# APA106_uno_shield.net
KiCad netlist of a schematic drawn in EAGLE
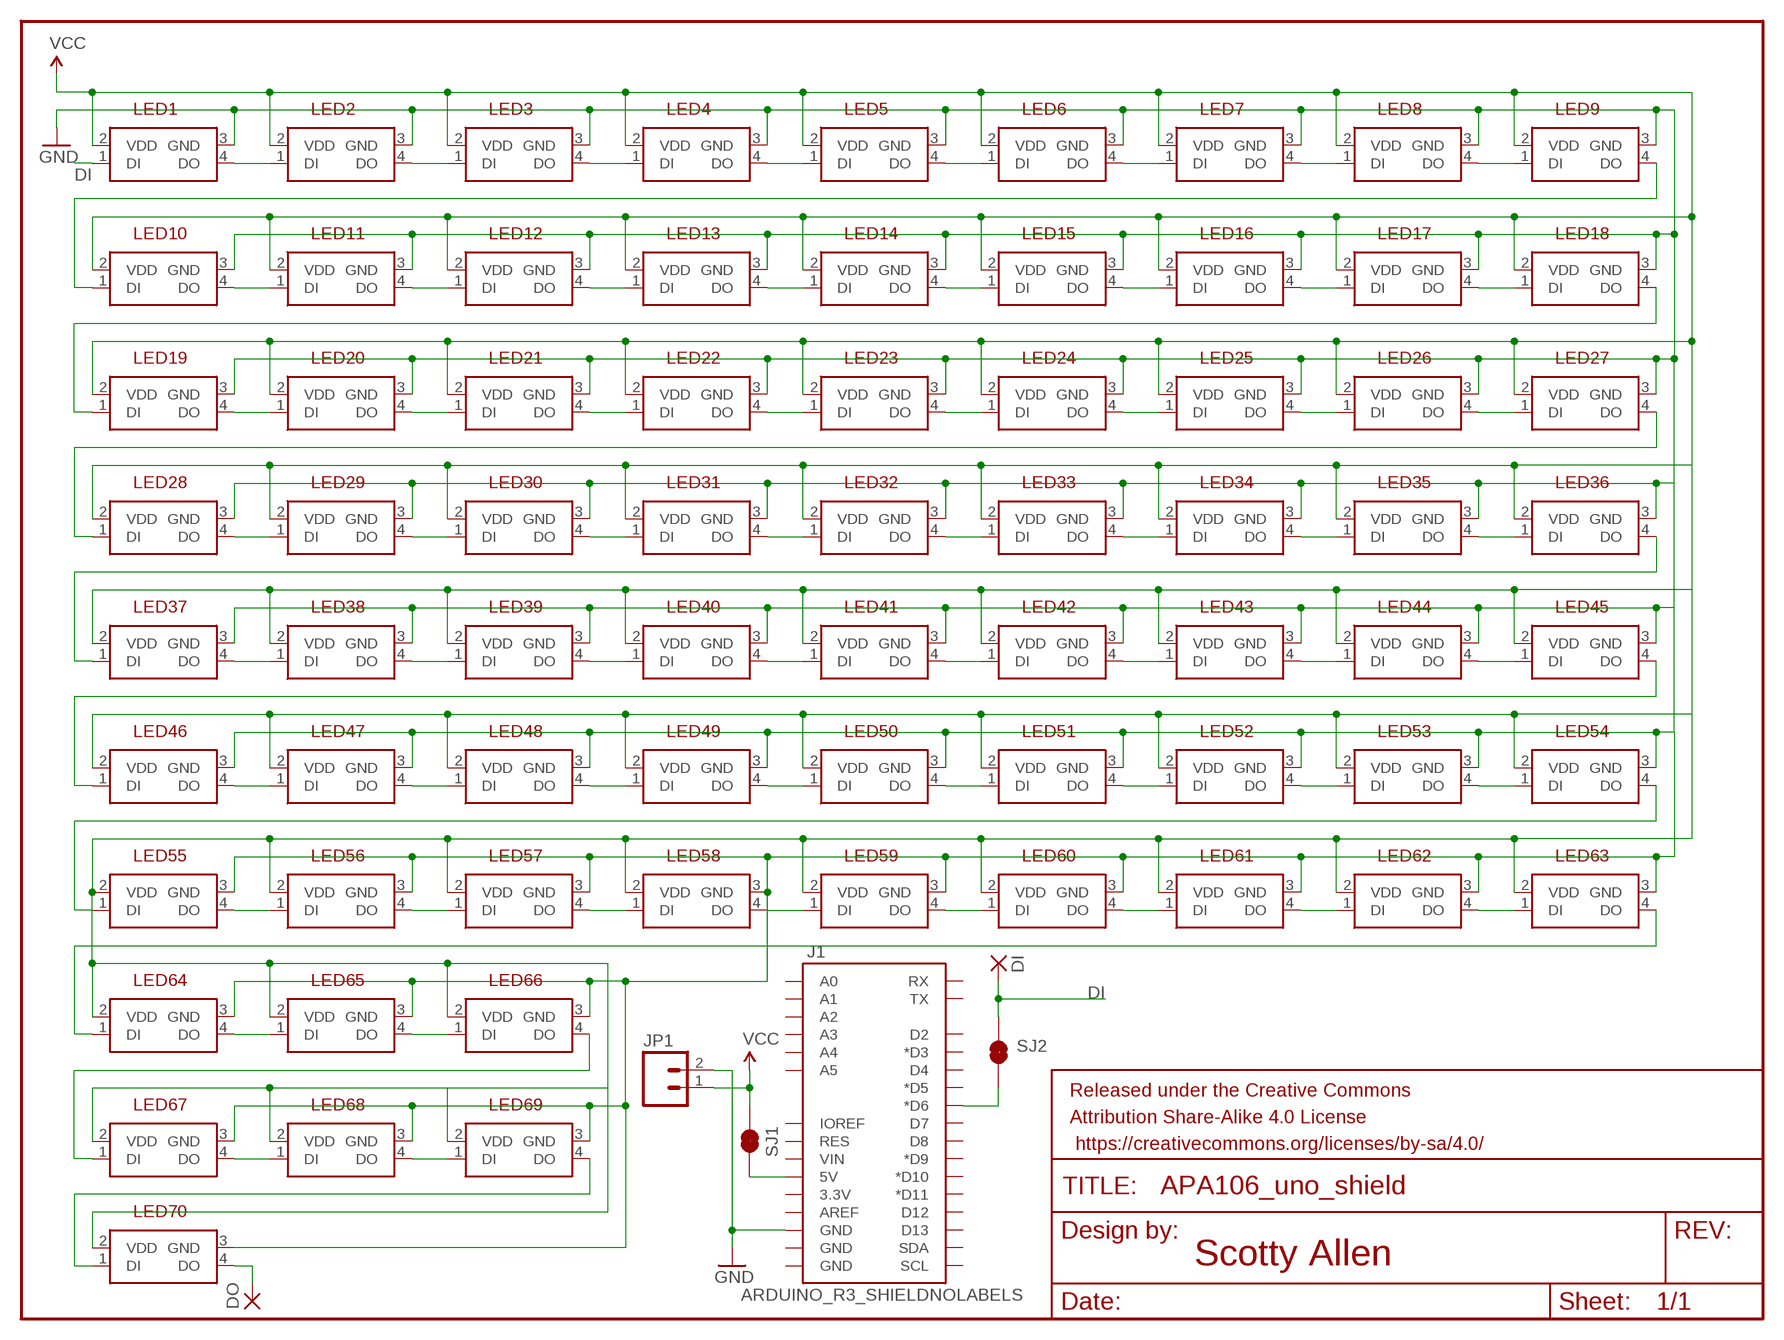
[diagram p0: schematic, sheet 1]

(export (version "E")
  (design (tool "Eeschema 10.0.6"))
  (components
    (comp (ref "DI")
      (value "1,6/0,9")
      (footprint "eagle-import:1,6_0,9")
      (libsource (lib "eagle-import") (part "1,6/0,9"))
    )
    (comp (ref "DO")
      (value "1,6/0,9")
      (footprint "eagle-import:1,6_0,9")
      (libsource (lib "eagle-import") (part "1,6/0,9"))
    )
    (comp (ref "FRAME1")
      (value "FRAME-LETTER")
      (footprint "eagle-import:CREATIVE_COMMONS")
      (libsource (lib "eagle-import") (part "FRAME-LETTER"))
    )
    (comp (ref "J1")
      (value "ARDUINO_R3_SHIELDNOLABELS")
      (footprint "eagle-import:UNO_R3_SHIELD_NOLABELS")
      (libsource (lib "eagle-import") (part "ARDUINO_R3_SHIELDNOLABELS"))
    )
    (comp (ref "JP1")
      (value "M02PTH")
      (footprint "eagle-import:1X02")
      (libsource (lib "eagle-import") (part "M02PTH"))
    )
    (comp (ref "LED1")
      (value "LED-APA106HOLE-OFFSET")
      (footprint "eagle-import:LED-5MM-4PIN-HOLE-OFFSET")
      (libsource (lib "eagle-import") (part "LED-APA106HOLE-OFFSET"))
    )
    (comp (ref "LED2")
      (value "LED-APA106HOLE-OFFSET")
      (footprint "eagle-import:LED-5MM-4PIN-HOLE-OFFSET")
      (libsource (lib "eagle-import") (part "LED-APA106HOLE-OFFSET"))
    )
    (comp (ref "LED3")
      (value "LED-APA106HOLE-OFFSET")
      (footprint "eagle-import:LED-5MM-4PIN-HOLE-OFFSET")
      (libsource (lib "eagle-import") (part "LED-APA106HOLE-OFFSET"))
    )
    (comp (ref "LED4")
      (value "LED-APA106HOLE-OFFSET")
      (footprint "eagle-import:LED-5MM-4PIN-HOLE-OFFSET")
      (libsource (lib "eagle-import") (part "LED-APA106HOLE-OFFSET"))
    )
    (comp (ref "LED5")
      (value "LED-APA106HOLE-OFFSET")
      (footprint "eagle-import:LED-5MM-4PIN-HOLE-OFFSET")
      (libsource (lib "eagle-import") (part "LED-APA106HOLE-OFFSET"))
    )
    (comp (ref "LED6")
      (value "LED-APA106HOLE-OFFSET")
      (footprint "eagle-import:LED-5MM-4PIN-HOLE-OFFSET")
      (libsource (lib "eagle-import") (part "LED-APA106HOLE-OFFSET"))
    )
    (comp (ref "LED7")
      (value "LED-APA106HOLE-OFFSET")
      (footprint "eagle-import:LED-5MM-4PIN-HOLE-OFFSET")
      (libsource (lib "eagle-import") (part "LED-APA106HOLE-OFFSET"))
    )
    (comp (ref "LED8")
      (value "LED-APA106HOLE-OFFSET")
      (footprint "eagle-import:LED-5MM-4PIN-HOLE-OFFSET")
      (libsource (lib "eagle-import") (part "LED-APA106HOLE-OFFSET"))
    )
    (comp (ref "LED9")
      (value "LED-APA106HOLE-OFFSET")
      (footprint "eagle-import:LED-5MM-4PIN-HOLE-OFFSET")
      (libsource (lib "eagle-import") (part "LED-APA106HOLE-OFFSET"))
    )
    (comp (ref "LED10")
      (value "LED-APA106HOLE-OFFSET")
      (footprint "eagle-import:LED-5MM-4PIN-HOLE-OFFSET")
      (libsource (lib "eagle-import") (part "LED-APA106HOLE-OFFSET"))
    )
    (comp (ref "LED11")
      (value "LED-APA106HOLE-OFFSET")
      (footprint "eagle-import:LED-5MM-4PIN-HOLE-OFFSET")
      (libsource (lib "eagle-import") (part "LED-APA106HOLE-OFFSET"))
    )
    (comp (ref "LED12")
      (value "LED-APA106HOLE-OFFSET")
      (footprint "eagle-import:LED-5MM-4PIN-HOLE-OFFSET")
      (libsource (lib "eagle-import") (part "LED-APA106HOLE-OFFSET"))
    )
    (comp (ref "LED13")
      (value "LED-APA106HOLE-OFFSET")
      (footprint "eagle-import:LED-5MM-4PIN-HOLE-OFFSET")
      (libsource (lib "eagle-import") (part "LED-APA106HOLE-OFFSET"))
    )
    (comp (ref "LED14")
      (value "LED-APA106HOLE-OFFSET")
      (footprint "eagle-import:LED-5MM-4PIN-HOLE-OFFSET")
      (libsource (lib "eagle-import") (part "LED-APA106HOLE-OFFSET"))
    )
    (comp (ref "LED15")
      (value "LED-APA106HOLE-OFFSET")
      (footprint "eagle-import:LED-5MM-4PIN-HOLE-OFFSET")
      (libsource (lib "eagle-import") (part "LED-APA106HOLE-OFFSET"))
    )
    (comp (ref "LED16")
      (value "LED-APA106HOLE-OFFSET")
      (footprint "eagle-import:LED-5MM-4PIN-HOLE-OFFSET")
      (libsource (lib "eagle-import") (part "LED-APA106HOLE-OFFSET"))
    )
    (comp (ref "LED17")
      (value "LED-APA106HOLE-OFFSET")
      (footprint "eagle-import:LED-5MM-4PIN-HOLE-OFFSET")
      (libsource (lib "eagle-import") (part "LED-APA106HOLE-OFFSET"))
    )
    (comp (ref "LED18")
      (value "LED-APA106HOLE-OFFSET")
      (footprint "eagle-import:LED-5MM-4PIN-HOLE-OFFSET")
      (libsource (lib "eagle-import") (part "LED-APA106HOLE-OFFSET"))
    )
    (comp (ref "LED19")
      (value "LED-APA106HOLE-OFFSET")
      (footprint "eagle-import:LED-5MM-4PIN-HOLE-OFFSET")
      (libsource (lib "eagle-import") (part "LED-APA106HOLE-OFFSET"))
    )
    (comp (ref "LED20")
      (value "LED-APA106HOLE-OFFSET")
      (footprint "eagle-import:LED-5MM-4PIN-HOLE-OFFSET")
      (libsource (lib "eagle-import") (part "LED-APA106HOLE-OFFSET"))
    )
    (comp (ref "LED21")
      (value "LED-APA106HOLE-OFFSET")
      (footprint "eagle-import:LED-5MM-4PIN-HOLE-OFFSET")
      (libsource (lib "eagle-import") (part "LED-APA106HOLE-OFFSET"))
    )
    (comp (ref "LED22")
      (value "LED-APA106HOLE-OFFSET")
      (footprint "eagle-import:LED-5MM-4PIN-HOLE-OFFSET")
      (libsource (lib "eagle-import") (part "LED-APA106HOLE-OFFSET"))
    )
    (comp (ref "LED23")
      (value "LED-APA106HOLE-OFFSET")
      (footprint "eagle-import:LED-5MM-4PIN-HOLE-OFFSET")
      (libsource (lib "eagle-import") (part "LED-APA106HOLE-OFFSET"))
    )
    (comp (ref "LED24")
      (value "LED-APA106HOLE-OFFSET")
      (footprint "eagle-import:LED-5MM-4PIN-HOLE-OFFSET")
      (libsource (lib "eagle-import") (part "LED-APA106HOLE-OFFSET"))
    )
    (comp (ref "LED25")
      (value "LED-APA106HOLE-OFFSET")
      (footprint "eagle-import:LED-5MM-4PIN-HOLE-OFFSET")
      (libsource (lib "eagle-import") (part "LED-APA106HOLE-OFFSET"))
    )
    (comp (ref "LED26")
      (value "LED-APA106HOLE-OFFSET")
      (footprint "eagle-import:LED-5MM-4PIN-HOLE-OFFSET")
      (libsource (lib "eagle-import") (part "LED-APA106HOLE-OFFSET"))
    )
    (comp (ref "LED27")
      (value "LED-APA106HOLE-OFFSET")
      (footprint "eagle-import:LED-5MM-4PIN-HOLE-OFFSET")
      (libsource (lib "eagle-import") (part "LED-APA106HOLE-OFFSET"))
    )
    (comp (ref "LED28")
      (value "LED-APA106HOLE-OFFSET")
      (footprint "eagle-import:LED-5MM-4PIN-HOLE-OFFSET")
      (libsource (lib "eagle-import") (part "LED-APA106HOLE-OFFSET"))
    )
    (comp (ref "LED29")
      (value "LED-APA106HOLE-OFFSET")
      (footprint "eagle-import:LED-5MM-4PIN-HOLE-OFFSET")
      (libsource (lib "eagle-import") (part "LED-APA106HOLE-OFFSET"))
    )
    (comp (ref "LED30")
      (value "LED-APA106HOLE-OFFSET")
      (footprint "eagle-import:LED-5MM-4PIN-HOLE-OFFSET")
      (libsource (lib "eagle-import") (part "LED-APA106HOLE-OFFSET"))
    )
    (comp (ref "LED31")
      (value "LED-APA106HOLE-OFFSET")
      (footprint "eagle-import:LED-5MM-4PIN-HOLE-OFFSET")
      (libsource (lib "eagle-import") (part "LED-APA106HOLE-OFFSET"))
    )
    (comp (ref "LED32")
      (value "LED-APA106HOLE-OFFSET")
      (footprint "eagle-import:LED-5MM-4PIN-HOLE-OFFSET")
      (libsource (lib "eagle-import") (part "LED-APA106HOLE-OFFSET"))
    )
    (comp (ref "LED33")
      (value "LED-APA106HOLE-OFFSET")
      (footprint "eagle-import:LED-5MM-4PIN-HOLE-OFFSET")
      (libsource (lib "eagle-import") (part "LED-APA106HOLE-OFFSET"))
    )
    (comp (ref "LED34")
      (value "LED-APA106HOLE-OFFSET")
      (footprint "eagle-import:LED-5MM-4PIN-HOLE-OFFSET")
      (libsource (lib "eagle-import") (part "LED-APA106HOLE-OFFSET"))
    )
    (comp (ref "LED35")
      (value "LED-APA106HOLE-OFFSET")
      (footprint "eagle-import:LED-5MM-4PIN-HOLE-OFFSET")
      (libsource (lib "eagle-import") (part "LED-APA106HOLE-OFFSET"))
    )
    (comp (ref "LED36")
      (value "LED-APA106HOLE-OFFSET")
      (footprint "eagle-import:LED-5MM-4PIN-HOLE-OFFSET")
      (libsource (lib "eagle-import") (part "LED-APA106HOLE-OFFSET"))
    )
    (comp (ref "LED37")
      (value "LED-APA106HOLE-OFFSET")
      (footprint "eagle-import:LED-5MM-4PIN-HOLE-OFFSET")
      (libsource (lib "eagle-import") (part "LED-APA106HOLE-OFFSET"))
    )
    (comp (ref "LED38")
      (value "LED-APA106HOLE-OFFSET")
      (footprint "eagle-import:LED-5MM-4PIN-HOLE-OFFSET")
      (libsource (lib "eagle-import") (part "LED-APA106HOLE-OFFSET"))
    )
    (comp (ref "LED39")
      (value "LED-APA106HOLE-OFFSET")
      (footprint "eagle-import:LED-5MM-4PIN-HOLE-OFFSET")
      (libsource (lib "eagle-import") (part "LED-APA106HOLE-OFFSET"))
    )
    (comp (ref "LED40")
      (value "LED-APA106HOLE-OFFSET")
      (footprint "eagle-import:LED-5MM-4PIN-HOLE-OFFSET")
      (libsource (lib "eagle-import") (part "LED-APA106HOLE-OFFSET"))
    )
    (comp (ref "LED41")
      (value "LED-APA106HOLE-OFFSET")
      (footprint "eagle-import:LED-5MM-4PIN-HOLE-OFFSET")
      (libsource (lib "eagle-import") (part "LED-APA106HOLE-OFFSET"))
    )
    (comp (ref "LED42")
      (value "LED-APA106HOLE-OFFSET")
      (footprint "eagle-import:LED-5MM-4PIN-HOLE-OFFSET")
      (libsource (lib "eagle-import") (part "LED-APA106HOLE-OFFSET"))
    )
    (comp (ref "LED43")
      (value "LED-APA106HOLE-OFFSET")
      (footprint "eagle-import:LED-5MM-4PIN-HOLE-OFFSET")
      (libsource (lib "eagle-import") (part "LED-APA106HOLE-OFFSET"))
    )
    (comp (ref "LED44")
      (value "LED-APA106HOLE-OFFSET")
      (footprint "eagle-import:LED-5MM-4PIN-HOLE-OFFSET")
      (libsource (lib "eagle-import") (part "LED-APA106HOLE-OFFSET"))
    )
    (comp (ref "LED45")
      (value "LED-APA106HOLE-OFFSET")
      (footprint "eagle-import:LED-5MM-4PIN-HOLE-OFFSET")
      (libsource (lib "eagle-import") (part "LED-APA106HOLE-OFFSET"))
    )
    (comp (ref "LED46")
      (value "LED-APA106HOLE-OFFSET")
      (footprint "eagle-import:LED-5MM-4PIN-HOLE-OFFSET")
      (libsource (lib "eagle-import") (part "LED-APA106HOLE-OFFSET"))
    )
    (comp (ref "LED47")
      (value "LED-APA106HOLE-OFFSET")
      (footprint "eagle-import:LED-5MM-4PIN-HOLE-OFFSET")
      (libsource (lib "eagle-import") (part "LED-APA106HOLE-OFFSET"))
    )
    (comp (ref "LED48")
      (value "LED-APA106HOLE-OFFSET")
      (footprint "eagle-import:LED-5MM-4PIN-HOLE-OFFSET")
      (libsource (lib "eagle-import") (part "LED-APA106HOLE-OFFSET"))
    )
    (comp (ref "LED49")
      (value "LED-APA106HOLE-OFFSET")
      (footprint "eagle-import:LED-5MM-4PIN-HOLE-OFFSET")
      (libsource (lib "eagle-import") (part "LED-APA106HOLE-OFFSET"))
    )
    (comp (ref "LED50")
      (value "LED-APA106HOLE-OFFSET")
      (footprint "eagle-import:LED-5MM-4PIN-HOLE-OFFSET")
      (libsource (lib "eagle-import") (part "LED-APA106HOLE-OFFSET"))
    )
    (comp (ref "LED51")
      (value "LED-APA106HOLE-OFFSET")
      (footprint "eagle-import:LED-5MM-4PIN-HOLE-OFFSET")
      (libsource (lib "eagle-import") (part "LED-APA106HOLE-OFFSET"))
    )
    (comp (ref "LED52")
      (value "LED-APA106HOLE-OFFSET")
      (footprint "eagle-import:LED-5MM-4PIN-HOLE-OFFSET")
      (libsource (lib "eagle-import") (part "LED-APA106HOLE-OFFSET"))
    )
    (comp (ref "LED53")
      (value "LED-APA106HOLE-OFFSET")
      (footprint "eagle-import:LED-5MM-4PIN-HOLE-OFFSET")
      (libsource (lib "eagle-import") (part "LED-APA106HOLE-OFFSET"))
    )
    (comp (ref "LED54")
      (value "LED-APA106HOLE-OFFSET")
      (footprint "eagle-import:LED-5MM-4PIN-HOLE-OFFSET")
      (libsource (lib "eagle-import") (part "LED-APA106HOLE-OFFSET"))
    )
    (comp (ref "LED55")
      (value "LED-APA106HOLE-OFFSET")
      (footprint "eagle-import:LED-5MM-4PIN-HOLE-OFFSET")
      (libsource (lib "eagle-import") (part "LED-APA106HOLE-OFFSET"))
    )
    (comp (ref "LED56")
      (value "LED-APA106HOLE-OFFSET")
      (footprint "eagle-import:LED-5MM-4PIN-HOLE-OFFSET")
      (libsource (lib "eagle-import") (part "LED-APA106HOLE-OFFSET"))
    )
    (comp (ref "LED57")
      (value "LED-APA106HOLE-OFFSET")
      (footprint "eagle-import:LED-5MM-4PIN-HOLE-OFFSET")
      (libsource (lib "eagle-import") (part "LED-APA106HOLE-OFFSET"))
    )
    (comp (ref "LED58")
      (value "LED-APA106HOLE-OFFSET")
      (footprint "eagle-import:LED-5MM-4PIN-HOLE-OFFSET")
      (libsource (lib "eagle-import") (part "LED-APA106HOLE-OFFSET"))
    )
    (comp (ref "LED59")
      (value "LED-APA106HOLE-OFFSET")
      (footprint "eagle-import:LED-5MM-4PIN-HOLE-OFFSET")
      (libsource (lib "eagle-import") (part "LED-APA106HOLE-OFFSET"))
    )
    (comp (ref "LED60")
      (value "LED-APA106HOLE-OFFSET")
      (footprint "eagle-import:LED-5MM-4PIN-HOLE-OFFSET")
      (libsource (lib "eagle-import") (part "LED-APA106HOLE-OFFSET"))
    )
    (comp (ref "LED61")
      (value "LED-APA106HOLE-OFFSET")
      (footprint "eagle-import:LED-5MM-4PIN-HOLE-OFFSET")
      (libsource (lib "eagle-import") (part "LED-APA106HOLE-OFFSET"))
    )
    (comp (ref "LED62")
      (value "LED-APA106HOLE-OFFSET")
      (footprint "eagle-import:LED-5MM-4PIN-HOLE-OFFSET")
      (libsource (lib "eagle-import") (part "LED-APA106HOLE-OFFSET"))
    )
    (comp (ref "LED63")
      (value "LED-APA106HOLE-OFFSET")
      (footprint "eagle-import:LED-5MM-4PIN-HOLE-OFFSET")
      (libsource (lib "eagle-import") (part "LED-APA106HOLE-OFFSET"))
    )
    (comp (ref "LED64")
      (value "LED-APA106HOLE-OFFSET")
      (footprint "eagle-import:LED-5MM-4PIN-HOLE-OFFSET")
      (libsource (lib "eagle-import") (part "LED-APA106HOLE-OFFSET"))
    )
    (comp (ref "LED65")
      (value "LED-APA106HOLE-OFFSET")
      (footprint "eagle-import:LED-5MM-4PIN-HOLE-OFFSET")
      (libsource (lib "eagle-import") (part "LED-APA106HOLE-OFFSET"))
    )
    (comp (ref "LED66")
      (value "LED-APA106HOLE-OFFSET")
      (footprint "eagle-import:LED-5MM-4PIN-HOLE-OFFSET")
      (libsource (lib "eagle-import") (part "LED-APA106HOLE-OFFSET"))
    )
    (comp (ref "LED67")
      (value "LED-APA106HOLE-OFFSET")
      (footprint "eagle-import:LED-5MM-4PIN-HOLE-OFFSET")
      (libsource (lib "eagle-import") (part "LED-APA106HOLE-OFFSET"))
    )
    (comp (ref "LED68")
      (value "LED-APA106HOLE-OFFSET")
      (footprint "eagle-import:LED-5MM-4PIN-HOLE-OFFSET")
      (libsource (lib "eagle-import") (part "LED-APA106HOLE-OFFSET"))
    )
    (comp (ref "LED69")
      (value "LED-APA106HOLE-OFFSET")
      (footprint "eagle-import:LED-5MM-4PIN-HOLE-OFFSET")
      (libsource (lib "eagle-import") (part "LED-APA106HOLE-OFFSET"))
    )
    (comp (ref "LED70")
      (value "LED-APA106HOLE-OFFSET")
      (footprint "eagle-import:LED-5MM-4PIN-HOLE-OFFSET")
      (libsource (lib "eagle-import") (part "LED-APA106HOLE-OFFSET"))
    )
    (comp (ref "SJ1")
      (value "JUMPER-PAD-2-NC_BY_TRACENO_SILK")
      (footprint "eagle-import:PAD-JUMPER-2-NC_BY_TRACE_NO_SILK")
      (libsource (lib "eagle-import") (part "JUMPER-PAD-2-NC_BY_TRACENO_SILK"))
    )
    (comp (ref "SJ2")
      (value "JUMPER-PAD-2-NC_BY_TRACENO_SILK")
      (footprint "eagle-import:PAD-JUMPER-2-NC_BY_TRACE_NO_SILK")
      (libsource (lib "eagle-import") (part "JUMPER-PAD-2-NC_BY_TRACENO_SILK"))
    )
  )
  (nets
    (net (code "1") (name "/DI") (class "Default")
      (node (ref "DI") (pin "1") (pinfunction "P_1") (pintype "passive"))
      (node (ref "LED1") (pin "1") (pinfunction "DI_1") (pintype "input"))
      (node (ref "SJ2") (pin "2") (pinfunction "2_2") (pintype "passive"))
    )
    (net (code "2") (name "GND") (class "Default")
      (node (ref "J1") (pin "GND@2") (pinfunction "GND_GND@2") (pintype "bidirectional"))
      (node (ref "JP1") (pin "2") (pinfunction "2_2") (pintype "passive"))
      (node (ref "LED1") (pin "3") (pinfunction "GND_3") (pintype "power_in"))
      (node (ref "LED10") (pin "3") (pinfunction "GND_3") (pintype "power_in"))
      (node (ref "LED11") (pin "3") (pinfunction "GND_3") (pintype "power_in"))
      (node (ref "LED12") (pin "3") (pinfunction "GND_3") (pintype "power_in"))
      (node (ref "LED13") (pin "3") (pinfunction "GND_3") (pintype "power_in"))
      (node (ref "LED14") (pin "3") (pinfunction "GND_3") (pintype "power_in"))
      (node (ref "LED15") (pin "3") (pinfunction "GND_3") (pintype "power_in"))
      (node (ref "LED16") (pin "3") (pinfunction "GND_3") (pintype "power_in"))
      (node (ref "LED17") (pin "3") (pinfunction "GND_3") (pintype "power_in"))
      (node (ref "LED18") (pin "3") (pinfunction "GND_3") (pintype "power_in"))
      (node (ref "LED19") (pin "3") (pinfunction "GND_3") (pintype "power_in"))
      (node (ref "LED2") (pin "3") (pinfunction "GND_3") (pintype "power_in"))
      (node (ref "LED20") (pin "3") (pinfunction "GND_3") (pintype "power_in"))
      (node (ref "LED21") (pin "3") (pinfunction "GND_3") (pintype "power_in"))
      (node (ref "LED22") (pin "3") (pinfunction "GND_3") (pintype "power_in"))
      (node (ref "LED23") (pin "3") (pinfunction "GND_3") (pintype "power_in"))
      (node (ref "LED24") (pin "3") (pinfunction "GND_3") (pintype "power_in"))
      (node (ref "LED25") (pin "3") (pinfunction "GND_3") (pintype "power_in"))
      (node (ref "LED26") (pin "3") (pinfunction "GND_3") (pintype "power_in"))
      (node (ref "LED27") (pin "3") (pinfunction "GND_3") (pintype "power_in"))
      (node (ref "LED28") (pin "3") (pinfunction "GND_3") (pintype "power_in"))
      (node (ref "LED29") (pin "3") (pinfunction "GND_3") (pintype "power_in"))
      (node (ref "LED3") (pin "3") (pinfunction "GND_3") (pintype "power_in"))
      (node (ref "LED30") (pin "3") (pinfunction "GND_3") (pintype "power_in"))
      (node (ref "LED31") (pin "3") (pinfunction "GND_3") (pintype "power_in"))
      (node (ref "LED32") (pin "3") (pinfunction "GND_3") (pintype "power_in"))
      (node (ref "LED33") (pin "3") (pinfunction "GND_3") (pintype "power_in"))
      (node (ref "LED34") (pin "3") (pinfunction "GND_3") (pintype "power_in"))
      (node (ref "LED35") (pin "3") (pinfunction "GND_3") (pintype "power_in"))
      (node (ref "LED36") (pin "3") (pinfunction "GND_3") (pintype "power_in"))
      (node (ref "LED37") (pin "3") (pinfunction "GND_3") (pintype "power_in"))
      (node (ref "LED38") (pin "3") (pinfunction "GND_3") (pintype "power_in"))
      (node (ref "LED39") (pin "3") (pinfunction "GND_3") (pintype "power_in"))
      (node (ref "LED4") (pin "3") (pinfunction "GND_3") (pintype "power_in"))
      (node (ref "LED40") (pin "3") (pinfunction "GND_3") (pintype "power_in"))
      (node (ref "LED41") (pin "3") (pinfunction "GND_3") (pintype "power_in"))
      (node (ref "LED42") (pin "3") (pinfunction "GND_3") (pintype "power_in"))
      (node (ref "LED43") (pin "3") (pinfunction "GND_3") (pintype "power_in"))
      (node (ref "LED44") (pin "3") (pinfunction "GND_3") (pintype "power_in"))
      (node (ref "LED45") (pin "3") (pinfunction "GND_3") (pintype "power_in"))
      (node (ref "LED46") (pin "3") (pinfunction "GND_3") (pintype "power_in"))
      (node (ref "LED47") (pin "3") (pinfunction "GND_3") (pintype "power_in"))
      (node (ref "LED48") (pin "3") (pinfunction "GND_3") (pintype "power_in"))
      (node (ref "LED49") (pin "3") (pinfunction "GND_3") (pintype "power_in"))
      (node (ref "LED5") (pin "3") (pinfunction "GND_3") (pintype "power_in"))
      (node (ref "LED50") (pin "3") (pinfunction "GND_3") (pintype "power_in"))
      (node (ref "LED51") (pin "3") (pinfunction "GND_3") (pintype "power_in"))
      (node (ref "LED52") (pin "3") (pinfunction "GND_3") (pintype "power_in"))
      (node (ref "LED53") (pin "3") (pinfunction "GND_3") (pintype "power_in"))
      (node (ref "LED54") (pin "3") (pinfunction "GND_3") (pintype "power_in"))
      (node (ref "LED55") (pin "3") (pinfunction "GND_3") (pintype "power_in"))
      (node (ref "LED56") (pin "3") (pinfunction "GND_3") (pintype "power_in"))
      (node (ref "LED57") (pin "3") (pinfunction "GND_3") (pintype "power_in"))
      (node (ref "LED58") (pin "3") (pinfunction "GND_3") (pintype "power_in"))
      (node (ref "LED59") (pin "3") (pinfunction "GND_3") (pintype "power_in"))
      (node (ref "LED6") (pin "3") (pinfunction "GND_3") (pintype "power_in"))
      (node (ref "LED60") (pin "3") (pinfunction "GND_3") (pintype "power_in"))
      (node (ref "LED61") (pin "3") (pinfunction "GND_3") (pintype "power_in"))
      (node (ref "LED62") (pin "3") (pinfunction "GND_3") (pintype "power_in"))
      (node (ref "LED63") (pin "3") (pinfunction "GND_3") (pintype "power_in"))
      (node (ref "LED64") (pin "3") (pinfunction "GND_3") (pintype "power_in"))
      (node (ref "LED65") (pin "3") (pinfunction "GND_3") (pintype "power_in"))
      (node (ref "LED66") (pin "3") (pinfunction "GND_3") (pintype "power_in"))
      (node (ref "LED67") (pin "3") (pinfunction "GND_3") (pintype "power_in"))
      (node (ref "LED68") (pin "3") (pinfunction "GND_3") (pintype "power_in"))
      (node (ref "LED69") (pin "3") (pinfunction "GND_3") (pintype "power_in"))
      (node (ref "LED7") (pin "3") (pinfunction "GND_3") (pintype "power_in"))
      (node (ref "LED70") (pin "3") (pinfunction "GND_3") (pintype "power_in"))
      (node (ref "LED8") (pin "3") (pinfunction "GND_3") (pintype "power_in"))
      (node (ref "LED9") (pin "3") (pinfunction "GND_3") (pintype "power_in"))
    )
    (net (code "3") (name "Net-(DO-P)") (class "Default")
      (node (ref "DO") (pin "1") (pinfunction "P_1") (pintype "passive"))
      (node (ref "LED70") (pin "4") (pinfunction "DO_4") (pintype "output"))
    )
    (net (code "4") (name "Net-(J1-*D6)") (class "Default")
      (node (ref "J1") (pin "D6") (pinfunction "*D6_D6") (pintype "bidirectional"))
      (node (ref "SJ2") (pin "1") (pinfunction "1_1") (pintype "passive"))
    )
    (net (code "5") (name "Net-(J1-Pad5V)") (class "Default")
      (node (ref "J1") (pin "5V") (pinfunction "5V_5V") (pintype "bidirectional"))
      (node (ref "SJ1") (pin "1") (pinfunction "1_1") (pintype "passive"))
    )
    (net (code "6") (name "Net-(LED1-DO)") (class "Default")
      (node (ref "LED1") (pin "4") (pinfunction "DO_4") (pintype "output"))
      (node (ref "LED2") (pin "1") (pinfunction "DI_1") (pintype "input"))
    )
    (net (code "7") (name "Net-(LED2-DO)") (class "Default")
      (node (ref "LED2") (pin "4") (pinfunction "DO_4") (pintype "output"))
      (node (ref "LED3") (pin "1") (pinfunction "DI_1") (pintype "input"))
    )
    (net (code "8") (name "Net-(LED3-DO)") (class "Default")
      (node (ref "LED3") (pin "4") (pinfunction "DO_4") (pintype "output"))
      (node (ref "LED4") (pin "1") (pinfunction "DI_1") (pintype "input"))
    )
    (net (code "9") (name "Net-(LED4-DO)") (class "Default")
      (node (ref "LED4") (pin "4") (pinfunction "DO_4") (pintype "output"))
      (node (ref "LED5") (pin "1") (pinfunction "DI_1") (pintype "input"))
    )
    (net (code "10") (name "Net-(LED5-DO)") (class "Default")
      (node (ref "LED5") (pin "4") (pinfunction "DO_4") (pintype "output"))
      (node (ref "LED6") (pin "1") (pinfunction "DI_1") (pintype "input"))
    )
    (net (code "11") (name "Net-(LED6-DO)") (class "Default")
      (node (ref "LED6") (pin "4") (pinfunction "DO_4") (pintype "output"))
      (node (ref "LED7") (pin "1") (pinfunction "DI_1") (pintype "input"))
    )
    (net (code "12") (name "Net-(LED7-DO)") (class "Default")
      (node (ref "LED7") (pin "4") (pinfunction "DO_4") (pintype "output"))
      (node (ref "LED8") (pin "1") (pinfunction "DI_1") (pintype "input"))
    )
    (net (code "13") (name "Net-(LED8-DO)") (class "Default")
      (node (ref "LED8") (pin "4") (pinfunction "DO_4") (pintype "output"))
      (node (ref "LED9") (pin "1") (pinfunction "DI_1") (pintype "input"))
    )
    (net (code "14") (name "Net-(LED10-DI)") (class "Default")
      (node (ref "LED10") (pin "1") (pinfunction "DI_1") (pintype "input"))
      (node (ref "LED9") (pin "4") (pinfunction "DO_4") (pintype "output"))
    )
    (net (code "15") (name "Net-(LED10-DO)") (class "Default")
      (node (ref "LED10") (pin "4") (pinfunction "DO_4") (pintype "output"))
      (node (ref "LED11") (pin "1") (pinfunction "DI_1") (pintype "input"))
    )
    (net (code "16") (name "Net-(LED11-DO)") (class "Default")
      (node (ref "LED11") (pin "4") (pinfunction "DO_4") (pintype "output"))
      (node (ref "LED12") (pin "1") (pinfunction "DI_1") (pintype "input"))
    )
    (net (code "17") (name "Net-(LED12-DO)") (class "Default")
      (node (ref "LED12") (pin "4") (pinfunction "DO_4") (pintype "output"))
      (node (ref "LED13") (pin "1") (pinfunction "DI_1") (pintype "input"))
    )
    (net (code "18") (name "Net-(LED13-DO)") (class "Default")
      (node (ref "LED13") (pin "4") (pinfunction "DO_4") (pintype "output"))
      (node (ref "LED14") (pin "1") (pinfunction "DI_1") (pintype "input"))
    )
    (net (code "19") (name "Net-(LED14-DO)") (class "Default")
      (node (ref "LED14") (pin "4") (pinfunction "DO_4") (pintype "output"))
      (node (ref "LED15") (pin "1") (pinfunction "DI_1") (pintype "input"))
    )
    (net (code "20") (name "Net-(LED15-DO)") (class "Default")
      (node (ref "LED15") (pin "4") (pinfunction "DO_4") (pintype "output"))
      (node (ref "LED16") (pin "1") (pinfunction "DI_1") (pintype "input"))
    )
    (net (code "21") (name "Net-(LED16-DO)") (class "Default")
      (node (ref "LED16") (pin "4") (pinfunction "DO_4") (pintype "output"))
      (node (ref "LED17") (pin "1") (pinfunction "DI_1") (pintype "input"))
    )
    (net (code "22") (name "Net-(LED17-DO)") (class "Default")
      (node (ref "LED17") (pin "4") (pinfunction "DO_4") (pintype "output"))
      (node (ref "LED18") (pin "1") (pinfunction "DI_1") (pintype "input"))
    )
    (net (code "23") (name "Net-(LED18-DO)") (class "Default")
      (node (ref "LED18") (pin "4") (pinfunction "DO_4") (pintype "output"))
      (node (ref "LED19") (pin "1") (pinfunction "DI_1") (pintype "input"))
    )
    (net (code "24") (name "Net-(LED19-DO)") (class "Default")
      (node (ref "LED19") (pin "4") (pinfunction "DO_4") (pintype "output"))
      (node (ref "LED20") (pin "1") (pinfunction "DI_1") (pintype "input"))
    )
    (net (code "25") (name "Net-(LED20-DO)") (class "Default")
      (node (ref "LED20") (pin "4") (pinfunction "DO_4") (pintype "output"))
      (node (ref "LED21") (pin "1") (pinfunction "DI_1") (pintype "input"))
    )
    (net (code "26") (name "Net-(LED21-DO)") (class "Default")
      (node (ref "LED21") (pin "4") (pinfunction "DO_4") (pintype "output"))
      (node (ref "LED22") (pin "1") (pinfunction "DI_1") (pintype "input"))
    )
    (net (code "27") (name "Net-(LED22-DO)") (class "Default")
      (node (ref "LED22") (pin "4") (pinfunction "DO_4") (pintype "output"))
      (node (ref "LED23") (pin "1") (pinfunction "DI_1") (pintype "input"))
    )
    (net (code "28") (name "Net-(LED23-DO)") (class "Default")
      (node (ref "LED23") (pin "4") (pinfunction "DO_4") (pintype "output"))
      (node (ref "LED24") (pin "1") (pinfunction "DI_1") (pintype "input"))
    )
    (net (code "29") (name "Net-(LED24-DO)") (class "Default")
      (node (ref "LED24") (pin "4") (pinfunction "DO_4") (pintype "output"))
      (node (ref "LED25") (pin "1") (pinfunction "DI_1") (pintype "input"))
    )
    (net (code "30") (name "Net-(LED25-DO)") (class "Default")
      (node (ref "LED25") (pin "4") (pinfunction "DO_4") (pintype "output"))
      (node (ref "LED26") (pin "1") (pinfunction "DI_1") (pintype "input"))
    )
    (net (code "31") (name "Net-(LED26-DO)") (class "Default")
      (node (ref "LED26") (pin "4") (pinfunction "DO_4") (pintype "output"))
      (node (ref "LED27") (pin "1") (pinfunction "DI_1") (pintype "input"))
    )
    (net (code "32") (name "Net-(LED27-DO)") (class "Default")
      (node (ref "LED27") (pin "4") (pinfunction "DO_4") (pintype "output"))
      (node (ref "LED28") (pin "1") (pinfunction "DI_1") (pintype "input"))
    )
    (net (code "33") (name "Net-(LED28-DO)") (class "Default")
      (node (ref "LED28") (pin "4") (pinfunction "DO_4") (pintype "output"))
      (node (ref "LED29") (pin "1") (pinfunction "DI_1") (pintype "input"))
    )
    (net (code "34") (name "Net-(LED29-DO)") (class "Default")
      (node (ref "LED29") (pin "4") (pinfunction "DO_4") (pintype "output"))
      (node (ref "LED30") (pin "1") (pinfunction "DI_1") (pintype "input"))
    )
    (net (code "35") (name "Net-(LED30-DO)") (class "Default")
      (node (ref "LED30") (pin "4") (pinfunction "DO_4") (pintype "output"))
      (node (ref "LED31") (pin "1") (pinfunction "DI_1") (pintype "input"))
    )
    (net (code "36") (name "Net-(LED31-DO)") (class "Default")
      (node (ref "LED31") (pin "4") (pinfunction "DO_4") (pintype "output"))
      (node (ref "LED32") (pin "1") (pinfunction "DI_1") (pintype "input"))
    )
    (net (code "37") (name "Net-(LED32-DO)") (class "Default")
      (node (ref "LED32") (pin "4") (pinfunction "DO_4") (pintype "output"))
      (node (ref "LED33") (pin "1") (pinfunction "DI_1") (pintype "input"))
    )
    (net (code "38") (name "Net-(LED33-DO)") (class "Default")
      (node (ref "LED33") (pin "4") (pinfunction "DO_4") (pintype "output"))
      (node (ref "LED34") (pin "1") (pinfunction "DI_1") (pintype "input"))
    )
    (net (code "39") (name "Net-(LED34-DO)") (class "Default")
      (node (ref "LED34") (pin "4") (pinfunction "DO_4") (pintype "output"))
      (node (ref "LED35") (pin "1") (pinfunction "DI_1") (pintype "input"))
    )
    (net (code "40") (name "Net-(LED35-DO)") (class "Default")
      (node (ref "LED35") (pin "4") (pinfunction "DO_4") (pintype "output"))
      (node (ref "LED36") (pin "1") (pinfunction "DI_1") (pintype "input"))
    )
    (net (code "41") (name "Net-(LED36-DO)") (class "Default")
      (node (ref "LED36") (pin "4") (pinfunction "DO_4") (pintype "output"))
      (node (ref "LED37") (pin "1") (pinfunction "DI_1") (pintype "input"))
    )
    (net (code "42") (name "Net-(LED37-DO)") (class "Default")
      (node (ref "LED37") (pin "4") (pinfunction "DO_4") (pintype "output"))
      (node (ref "LED38") (pin "1") (pinfunction "DI_1") (pintype "input"))
    )
    (net (code "43") (name "Net-(LED38-DO)") (class "Default")
      (node (ref "LED38") (pin "4") (pinfunction "DO_4") (pintype "output"))
      (node (ref "LED39") (pin "1") (pinfunction "DI_1") (pintype "input"))
    )
    (net (code "44") (name "Net-(LED39-DO)") (class "Default")
      (node (ref "LED39") (pin "4") (pinfunction "DO_4") (pintype "output"))
      (node (ref "LED40") (pin "1") (pinfunction "DI_1") (pintype "input"))
    )
    (net (code "45") (name "Net-(LED40-DO)") (class "Default")
      (node (ref "LED40") (pin "4") (pinfunction "DO_4") (pintype "output"))
      (node (ref "LED41") (pin "1") (pinfunction "DI_1") (pintype "input"))
    )
    (net (code "46") (name "Net-(LED41-DO)") (class "Default")
      (node (ref "LED41") (pin "4") (pinfunction "DO_4") (pintype "output"))
      (node (ref "LED42") (pin "1") (pinfunction "DI_1") (pintype "input"))
    )
    (net (code "47") (name "Net-(LED42-DO)") (class "Default")
      (node (ref "LED42") (pin "4") (pinfunction "DO_4") (pintype "output"))
      (node (ref "LED43") (pin "1") (pinfunction "DI_1") (pintype "input"))
    )
    (net (code "48") (name "Net-(LED43-DO)") (class "Default")
      (node (ref "LED43") (pin "4") (pinfunction "DO_4") (pintype "output"))
      (node (ref "LED44") (pin "1") (pinfunction "DI_1") (pintype "input"))
    )
    (net (code "49") (name "Net-(LED44-DO)") (class "Default")
      (node (ref "LED44") (pin "4") (pinfunction "DO_4") (pintype "output"))
      (node (ref "LED45") (pin "1") (pinfunction "DI_1") (pintype "input"))
    )
    (net (code "50") (name "Net-(LED45-DO)") (class "Default")
      (node (ref "LED45") (pin "4") (pinfunction "DO_4") (pintype "output"))
      (node (ref "LED46") (pin "1") (pinfunction "DI_1") (pintype "input"))
    )
    (net (code "51") (name "Net-(LED46-DO)") (class "Default")
      (node (ref "LED46") (pin "4") (pinfunction "DO_4") (pintype "output"))
      (node (ref "LED47") (pin "1") (pinfunction "DI_1") (pintype "input"))
    )
    (net (code "52") (name "Net-(LED47-DO)") (class "Default")
      (node (ref "LED47") (pin "4") (pinfunction "DO_4") (pintype "output"))
      (node (ref "LED48") (pin "1") (pinfunction "DI_1") (pintype "input"))
    )
    (net (code "53") (name "Net-(LED48-DO)") (class "Default")
      (node (ref "LED48") (pin "4") (pinfunction "DO_4") (pintype "output"))
      (node (ref "LED49") (pin "1") (pinfunction "DI_1") (pintype "input"))
    )
    (net (code "54") (name "Net-(LED49-DO)") (class "Default")
      (node (ref "LED49") (pin "4") (pinfunction "DO_4") (pintype "output"))
      (node (ref "LED50") (pin "1") (pinfunction "DI_1") (pintype "input"))
    )
    (net (code "55") (name "Net-(LED50-DO)") (class "Default")
      (node (ref "LED50") (pin "4") (pinfunction "DO_4") (pintype "output"))
      (node (ref "LED51") (pin "1") (pinfunction "DI_1") (pintype "input"))
    )
    (net (code "56") (name "Net-(LED51-DO)") (class "Default")
      (node (ref "LED51") (pin "4") (pinfunction "DO_4") (pintype "output"))
      (node (ref "LED52") (pin "1") (pinfunction "DI_1") (pintype "input"))
    )
    (net (code "57") (name "Net-(LED52-DO)") (class "Default")
      (node (ref "LED52") (pin "4") (pinfunction "DO_4") (pintype "output"))
      (node (ref "LED53") (pin "1") (pinfunction "DI_1") (pintype "input"))
    )
    (net (code "58") (name "Net-(LED53-DO)") (class "Default")
      (node (ref "LED53") (pin "4") (pinfunction "DO_4") (pintype "output"))
      (node (ref "LED54") (pin "1") (pinfunction "DI_1") (pintype "input"))
    )
    (net (code "59") (name "Net-(LED54-DO)") (class "Default")
      (node (ref "LED54") (pin "4") (pinfunction "DO_4") (pintype "output"))
      (node (ref "LED55") (pin "1") (pinfunction "DI_1") (pintype "input"))
    )
    (net (code "60") (name "Net-(LED55-DO)") (class "Default")
      (node (ref "LED55") (pin "4") (pinfunction "DO_4") (pintype "output"))
      (node (ref "LED56") (pin "1") (pinfunction "DI_1") (pintype "input"))
    )
    (net (code "61") (name "Net-(LED56-DO)") (class "Default")
      (node (ref "LED56") (pin "4") (pinfunction "DO_4") (pintype "output"))
      (node (ref "LED57") (pin "1") (pinfunction "DI_1") (pintype "input"))
    )
    (net (code "62") (name "Net-(LED57-DO)") (class "Default")
      (node (ref "LED57") (pin "4") (pinfunction "DO_4") (pintype "output"))
      (node (ref "LED58") (pin "1") (pinfunction "DI_1") (pintype "input"))
    )
    (net (code "63") (name "Net-(LED58-DO)") (class "Default")
      (node (ref "LED58") (pin "4") (pinfunction "DO_4") (pintype "output"))
      (node (ref "LED59") (pin "1") (pinfunction "DI_1") (pintype "input"))
    )
    (net (code "64") (name "Net-(LED59-DO)") (class "Default")
      (node (ref "LED59") (pin "4") (pinfunction "DO_4") (pintype "output"))
      (node (ref "LED60") (pin "1") (pinfunction "DI_1") (pintype "input"))
    )
    (net (code "65") (name "Net-(LED60-DO)") (class "Default")
      (node (ref "LED60") (pin "4") (pinfunction "DO_4") (pintype "output"))
      (node (ref "LED61") (pin "1") (pinfunction "DI_1") (pintype "input"))
    )
    (net (code "66") (name "Net-(LED61-DO)") (class "Default")
      (node (ref "LED61") (pin "4") (pinfunction "DO_4") (pintype "output"))
      (node (ref "LED62") (pin "1") (pinfunction "DI_1") (pintype "input"))
    )
    (net (code "67") (name "Net-(LED62-DO)") (class "Default")
      (node (ref "LED62") (pin "4") (pinfunction "DO_4") (pintype "output"))
      (node (ref "LED63") (pin "1") (pinfunction "DI_1") (pintype "input"))
    )
    (net (code "68") (name "Net-(LED63-DO)") (class "Default")
      (node (ref "LED63") (pin "4") (pinfunction "DO_4") (pintype "output"))
      (node (ref "LED64") (pin "1") (pinfunction "DI_1") (pintype "input"))
    )
    (net (code "69") (name "Net-(LED64-DO)") (class "Default")
      (node (ref "LED64") (pin "4") (pinfunction "DO_4") (pintype "output"))
      (node (ref "LED65") (pin "1") (pinfunction "DI_1") (pintype "input"))
    )
    (net (code "70") (name "Net-(LED65-DO)") (class "Default")
      (node (ref "LED65") (pin "4") (pinfunction "DO_4") (pintype "output"))
      (node (ref "LED66") (pin "1") (pinfunction "DI_1") (pintype "input"))
    )
    (net (code "71") (name "Net-(LED66-DO)") (class "Default")
      (node (ref "LED66") (pin "4") (pinfunction "DO_4") (pintype "output"))
      (node (ref "LED67") (pin "1") (pinfunction "DI_1") (pintype "input"))
    )
    (net (code "72") (name "Net-(LED67-DO)") (class "Default")
      (node (ref "LED67") (pin "4") (pinfunction "DO_4") (pintype "output"))
      (node (ref "LED68") (pin "1") (pinfunction "DI_1") (pintype "input"))
    )
    (net (code "73") (name "Net-(LED68-DO)") (class "Default")
      (node (ref "LED68") (pin "4") (pinfunction "DO_4") (pintype "output"))
      (node (ref "LED69") (pin "1") (pinfunction "DI_1") (pintype "input"))
    )
    (net (code "74") (name "Net-(LED69-DO)") (class "Default")
      (node (ref "LED69") (pin "4") (pinfunction "DO_4") (pintype "output"))
      (node (ref "LED70") (pin "1") (pinfunction "DI_1") (pintype "input"))
    )
    (net (code "75") (name "VCC") (class "Default")
      (node (ref "JP1") (pin "1") (pinfunction "1_1") (pintype "passive"))
      (node (ref "LED1") (pin "2") (pinfunction "VDD_2") (pintype "power_in"))
      (node (ref "LED10") (pin "2") (pinfunction "VDD_2") (pintype "power_in"))
      (node (ref "LED11") (pin "2") (pinfunction "VDD_2") (pintype "power_in"))
      (node (ref "LED12") (pin "2") (pinfunction "VDD_2") (pintype "power_in"))
      (node (ref "LED13") (pin "2") (pinfunction "VDD_2") (pintype "power_in"))
      (node (ref "LED14") (pin "2") (pinfunction "VDD_2") (pintype "power_in"))
      (node (ref "LED15") (pin "2") (pinfunction "VDD_2") (pintype "power_in"))
      (node (ref "LED16") (pin "2") (pinfunction "VDD_2") (pintype "power_in"))
      (node (ref "LED17") (pin "2") (pinfunction "VDD_2") (pintype "power_in"))
      (node (ref "LED18") (pin "2") (pinfunction "VDD_2") (pintype "power_in"))
      (node (ref "LED19") (pin "2") (pinfunction "VDD_2") (pintype "power_in"))
      (node (ref "LED2") (pin "2") (pinfunction "VDD_2") (pintype "power_in"))
      (node (ref "LED20") (pin "2") (pinfunction "VDD_2") (pintype "power_in"))
      (node (ref "LED21") (pin "2") (pinfunction "VDD_2") (pintype "power_in"))
      (node (ref "LED22") (pin "2") (pinfunction "VDD_2") (pintype "power_in"))
      (node (ref "LED23") (pin "2") (pinfunction "VDD_2") (pintype "power_in"))
      (node (ref "LED24") (pin "2") (pinfunction "VDD_2") (pintype "power_in"))
      (node (ref "LED25") (pin "2") (pinfunction "VDD_2") (pintype "power_in"))
      (node (ref "LED26") (pin "2") (pinfunction "VDD_2") (pintype "power_in"))
      (node (ref "LED27") (pin "2") (pinfunction "VDD_2") (pintype "power_in"))
      (node (ref "LED28") (pin "2") (pinfunction "VDD_2") (pintype "power_in"))
      (node (ref "LED29") (pin "2") (pinfunction "VDD_2") (pintype "power_in"))
      (node (ref "LED3") (pin "2") (pinfunction "VDD_2") (pintype "power_in"))
      (node (ref "LED30") (pin "2") (pinfunction "VDD_2") (pintype "power_in"))
      (node (ref "LED31") (pin "2") (pinfunction "VDD_2") (pintype "power_in"))
      (node (ref "LED32") (pin "2") (pinfunction "VDD_2") (pintype "power_in"))
      (node (ref "LED33") (pin "2") (pinfunction "VDD_2") (pintype "power_in"))
      (node (ref "LED34") (pin "2") (pinfunction "VDD_2") (pintype "power_in"))
      (node (ref "LED35") (pin "2") (pinfunction "VDD_2") (pintype "power_in"))
      (node (ref "LED36") (pin "2") (pinfunction "VDD_2") (pintype "power_in"))
      (node (ref "LED37") (pin "2") (pinfunction "VDD_2") (pintype "power_in"))
      (node (ref "LED38") (pin "2") (pinfunction "VDD_2") (pintype "power_in"))
      (node (ref "LED39") (pin "2") (pinfunction "VDD_2") (pintype "power_in"))
      (node (ref "LED4") (pin "2") (pinfunction "VDD_2") (pintype "power_in"))
      (node (ref "LED40") (pin "2") (pinfunction "VDD_2") (pintype "power_in"))
      (node (ref "LED41") (pin "2") (pinfunction "VDD_2") (pintype "power_in"))
      (node (ref "LED42") (pin "2") (pinfunction "VDD_2") (pintype "power_in"))
      (node (ref "LED43") (pin "2") (pinfunction "VDD_2") (pintype "power_in"))
      (node (ref "LED44") (pin "2") (pinfunction "VDD_2") (pintype "power_in"))
      (node (ref "LED45") (pin "2") (pinfunction "VDD_2") (pintype "power_in"))
      (node (ref "LED46") (pin "2") (pinfunction "VDD_2") (pintype "power_in"))
      (node (ref "LED47") (pin "2") (pinfunction "VDD_2") (pintype "power_in"))
      (node (ref "LED48") (pin "2") (pinfunction "VDD_2") (pintype "power_in"))
      (node (ref "LED49") (pin "2") (pinfunction "VDD_2") (pintype "power_in"))
      (node (ref "LED5") (pin "2") (pinfunction "VDD_2") (pintype "power_in"))
      (node (ref "LED50") (pin "2") (pinfunction "VDD_2") (pintype "power_in"))
      (node (ref "LED51") (pin "2") (pinfunction "VDD_2") (pintype "power_in"))
      (node (ref "LED52") (pin "2") (pinfunction "VDD_2") (pintype "power_in"))
      (node (ref "LED53") (pin "2") (pinfunction "VDD_2") (pintype "power_in"))
      (node (ref "LED54") (pin "2") (pinfunction "VDD_2") (pintype "power_in"))
      (node (ref "LED55") (pin "2") (pinfunction "VDD_2") (pintype "power_in"))
      (node (ref "LED56") (pin "2") (pinfunction "VDD_2") (pintype "power_in"))
      (node (ref "LED57") (pin "2") (pinfunction "VDD_2") (pintype "power_in"))
      (node (ref "LED58") (pin "2") (pinfunction "VDD_2") (pintype "power_in"))
      (node (ref "LED59") (pin "2") (pinfunction "VDD_2") (pintype "power_in"))
      (node (ref "LED6") (pin "2") (pinfunction "VDD_2") (pintype "power_in"))
      (node (ref "LED60") (pin "2") (pinfunction "VDD_2") (pintype "power_in"))
      (node (ref "LED61") (pin "2") (pinfunction "VDD_2") (pintype "power_in"))
      (node (ref "LED62") (pin "2") (pinfunction "VDD_2") (pintype "power_in"))
      (node (ref "LED63") (pin "2") (pinfunction "VDD_2") (pintype "power_in"))
      (node (ref "LED64") (pin "2") (pinfunction "VDD_2") (pintype "power_in"))
      (node (ref "LED65") (pin "2") (pinfunction "VDD_2") (pintype "power_in"))
      (node (ref "LED66") (pin "2") (pinfunction "VDD_2") (pintype "power_in"))
      (node (ref "LED67") (pin "2") (pinfunction "VDD_2") (pintype "power_in"))
      (node (ref "LED68") (pin "2") (pinfunction "VDD_2") (pintype "power_in"))
      (node (ref "LED69") (pin "2") (pinfunction "VDD_2") (pintype "power_in"))
      (node (ref "LED7") (pin "2") (pinfunction "VDD_2") (pintype "power_in"))
      (node (ref "LED70") (pin "2") (pinfunction "VDD_2") (pintype "power_in"))
      (node (ref "LED8") (pin "2") (pinfunction "VDD_2") (pintype "power_in"))
      (node (ref "LED9") (pin "2") (pinfunction "VDD_2") (pintype "power_in"))
      (node (ref "SJ1") (pin "2") (pinfunction "2_2") (pintype "passive"))
    )
    (net (code "76") (name "unconnected-(J1-*D3-PadD3)") (class "Default")
      (node (ref "J1") (pin "D3") (pinfunction "*D3_D3") (pintype "bidirectional"))
    )
    (net (code "77") (name "unconnected-(J1-*D5-PadD5)") (class "Default")
      (node (ref "J1") (pin "D5") (pinfunction "*D5_D5") (pintype "bidirectional"))
    )
    (net (code "78") (name "unconnected-(J1-*D9-PadD9)") (class "Default")
      (node (ref "J1") (pin "D9") (pinfunction "*D9_D9") (pintype "bidirectional"))
    )
    (net (code "79") (name "unconnected-(J1-*D10-PadD10)") (class "Default")
      (node (ref "J1") (pin "D10") (pinfunction "*D10_D10") (pintype "bidirectional"))
    )
    (net (code "80") (name "unconnected-(J1-*D11-PadD11)") (class "Default")
      (node (ref "J1") (pin "D11") (pinfunction "*D11_D11") (pintype "bidirectional"))
    )
    (net (code "81") (name "unconnected-(J1-GND-PadGND@0)") (class "Default")
      (node (ref "J1") (pin "GND@0") (pinfunction "GND_GND@0") (pintype "bidirectional"))
    )
    (net (code "82") (name "unconnected-(J1-GND-PadGND@1)") (class "Default")
      (node (ref "J1") (pin "GND@1") (pinfunction "GND_GND@1") (pintype "bidirectional"))
    )
    (net (code "83") (name "unconnected-(J1-Pad3.3V)") (class "Default")
      (node (ref "J1") (pin "3.3V") (pinfunction "3.3V_3.3V") (pintype "bidirectional"))
    )
    (net (code "84") (name "unconnected-(J1-PadA0)") (class "Default")
      (node (ref "J1") (pin "A0") (pinfunction "A0_A0") (pintype "bidirectional"))
    )
    (net (code "85") (name "unconnected-(J1-PadA1)") (class "Default")
      (node (ref "J1") (pin "A1") (pinfunction "A1_A1") (pintype "bidirectional"))
    )
    (net (code "86") (name "unconnected-(J1-PadA2)") (class "Default")
      (node (ref "J1") (pin "A2") (pinfunction "A2_A2") (pintype "bidirectional"))
    )
    (net (code "87") (name "unconnected-(J1-PadA3)") (class "Default")
      (node (ref "J1") (pin "A3") (pinfunction "A3_A3") (pintype "bidirectional"))
    )
    (net (code "88") (name "unconnected-(J1-PadA4)") (class "Default")
      (node (ref "J1") (pin "A4") (pinfunction "A4_A4") (pintype "bidirectional"))
    )
    (net (code "89") (name "unconnected-(J1-PadA5)") (class "Default")
      (node (ref "J1") (pin "A5") (pinfunction "A5_A5") (pintype "bidirectional"))
    )
    (net (code "90") (name "unconnected-(J1-PadAREF)") (class "Default")
      (node (ref "J1") (pin "AREF") (pinfunction "AREF_AREF") (pintype "bidirectional"))
    )
    (net (code "91") (name "unconnected-(J1-PadD2)") (class "Default")
      (node (ref "J1") (pin "D2") (pinfunction "D2_D2") (pintype "bidirectional"))
    )
    (net (code "92") (name "unconnected-(J1-PadD4)") (class "Default")
      (node (ref "J1") (pin "D4") (pinfunction "D4_D4") (pintype "bidirectional"))
    )
    (net (code "93") (name "unconnected-(J1-PadD7)") (class "Default")
      (node (ref "J1") (pin "D7") (pinfunction "D7_D7") (pintype "bidirectional"))
    )
    (net (code "94") (name "unconnected-(J1-PadD8)") (class "Default")
      (node (ref "J1") (pin "D8") (pinfunction "D8_D8") (pintype "bidirectional"))
    )
    (net (code "95") (name "unconnected-(J1-PadD12)") (class "Default")
      (node (ref "J1") (pin "D12") (pinfunction "D12_D12") (pintype "bidirectional"))
    )
    (net (code "96") (name "unconnected-(J1-PadD13)") (class "Default")
      (node (ref "J1") (pin "D13") (pinfunction "D13_D13") (pintype "bidirectional"))
    )
    (net (code "97") (name "unconnected-(J1-PadIOREF)") (class "Default")
      (node (ref "J1") (pin "IOREF") (pinfunction "IOREF_IOREF") (pintype "bidirectional"))
    )
    (net (code "98") (name "unconnected-(J1-PadRES)") (class "Default")
      (node (ref "J1") (pin "RES") (pinfunction "RES_RES") (pintype "bidirectional"))
    )
    (net (code "99") (name "unconnected-(J1-PadRX)") (class "Default")
      (node (ref "J1") (pin "RX") (pinfunction "RX_RX") (pintype "bidirectional"))
    )
    (net (code "100") (name "unconnected-(J1-PadSCL)") (class "Default")
      (node (ref "J1") (pin "SCL") (pinfunction "SCL_SCL") (pintype "bidirectional"))
    )
    (net (code "101") (name "unconnected-(J1-PadSDA)") (class "Default")
      (node (ref "J1") (pin "SDA") (pinfunction "SDA_SDA") (pintype "bidirectional"))
    )
    (net (code "102") (name "unconnected-(J1-PadTX)") (class "Default")
      (node (ref "J1") (pin "TX") (pinfunction "TX_TX") (pintype "bidirectional"))
    )
    (net (code "103") (name "unconnected-(J1-PadVIN)") (class "Default")
      (node (ref "J1") (pin "VIN") (pinfunction "VIN_VIN") (pintype "bidirectional"))
    )
  )
)
